# M239A.net
KiCad netlist of a schematic drawn in EAGLE
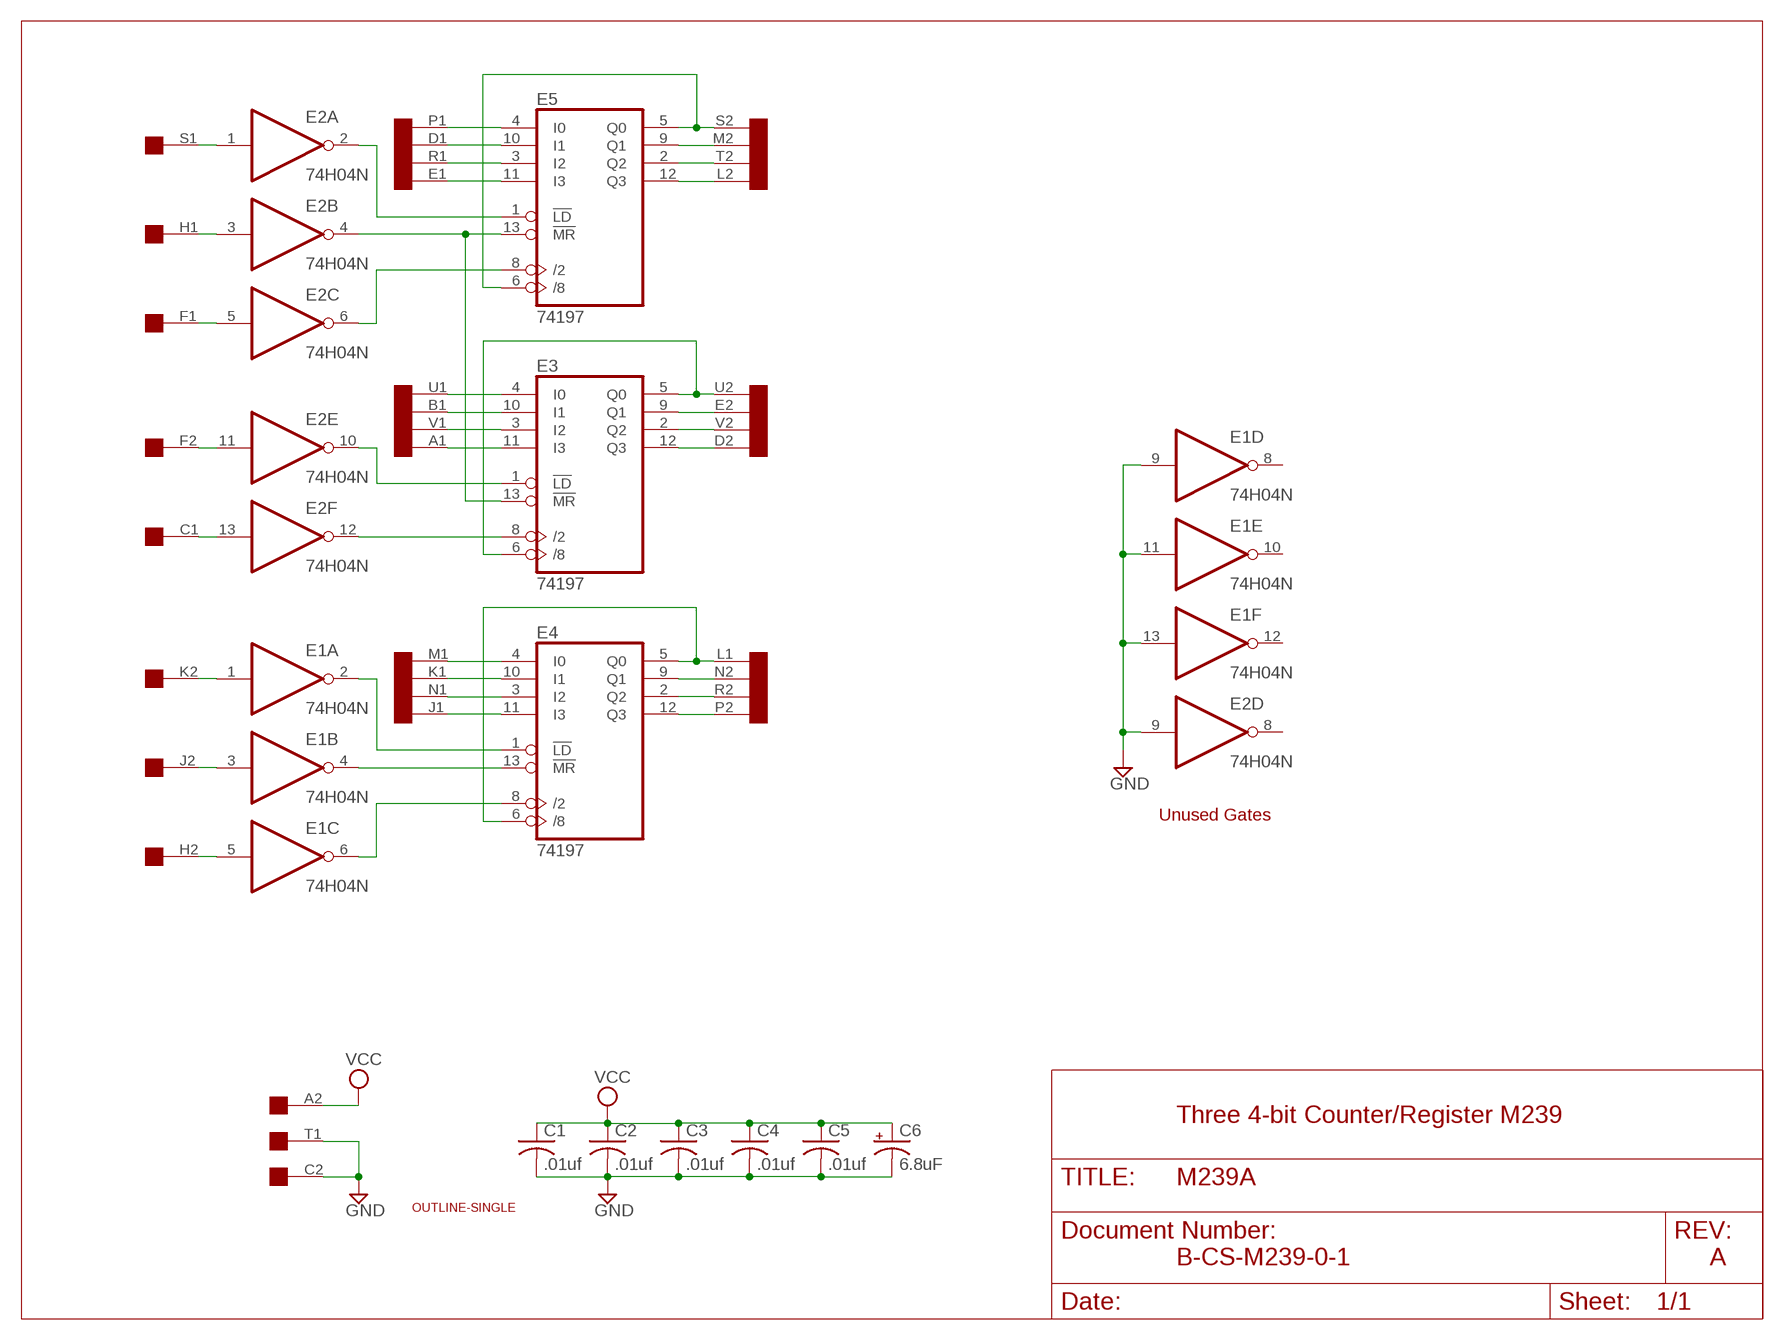
[diagram p0: schematic, sheet 1]

(export (version "E")
  (design (tool "Eeschema 10.0.6"))
  (components
    (comp (ref "C1")
      (value ".01uf")
      (footprint "eagle-import:C050-025X075")
      (libsource (lib "eagle-import") (part "C-US050-025X075"))
    )
    (comp (ref "C2")
      (value ".01uf")
      (footprint "eagle-import:C050-025X075")
      (libsource (lib "eagle-import") (part "C-US050-025X075"))
    )
    (comp (ref "C3")
      (value ".01uf")
      (footprint "eagle-import:C050-025X075")
      (libsource (lib "eagle-import") (part "C-US050-025X075"))
    )
    (comp (ref "C4")
      (value ".01uf")
      (footprint "eagle-import:C050-025X075")
      (libsource (lib "eagle-import") (part "C-US050-025X075"))
    )
    (comp (ref "C5")
      (value ".01uf")
      (footprint "eagle-import:C050-025X075")
      (libsource (lib "eagle-import") (part "C-US050-025X075"))
    )
    (comp (ref "C6")
      (value "6.8uF")
      (footprint "eagle-import:E22-6")
      (libsource (lib "eagle-import") (part "CPOL-USE22-6AXIAL"))
    )
    (comp (ref "E1")
      (value "74H04N")
      (footprint "eagle-import:DIL14")
      (libsource (lib "eagle-import") (part "7404N"))
    )
    (comp (ref "E2")
      (value "74H04N")
      (footprint "eagle-import:DIL14")
      (libsource (lib "eagle-import") (part "7404N"))
    )
    (comp (ref "E3")
      (value "74197")
      (footprint "eagle-import:DIL14")
      (libsource (lib "eagle-import") (part "74LS197"))
    )
    (comp (ref "E4")
      (value "74197")
      (footprint "eagle-import:DIL14")
      (libsource (lib "eagle-import") (part "74LS197"))
    )
    (comp (ref "E5")
      (value "74197")
      (footprint "eagle-import:DIL14")
      (libsource (lib "eagle-import") (part "74LS197"))
    )
    (comp (ref "U$1")
      (value "OUTLINE-SINGLE")
      (footprint "eagle-import:SINGLE")
      (libsource (lib "eagle-import") (part "OUTLINE-SINGLE"))
    )
    (comp (ref "U$4")
      (value "SINGLE")
      (footprint "eagle-import:EDGE-CON2")
      (libsource (lib "eagle-import") (part "SINGLE"))
    )
  )
  (nets
    (net (code "1") (name "GND") (class "Default")
      (node (ref "C1") (pin "2") (pinfunction "2_2") (pintype "passive"))
      (node (ref "C2") (pin "2") (pinfunction "2_2") (pintype "passive"))
      (node (ref "C3") (pin "2") (pinfunction "2_2") (pintype "passive"))
      (node (ref "C4") (pin "2") (pinfunction "2_2") (pintype "passive"))
      (node (ref "C5") (pin "2") (pinfunction "2_2") (pintype "passive"))
      (node (ref "C6") (pin "-") (pinfunction "-_-") (pintype "passive"))
      (node (ref "E1") (pin "11") (pinfunction "I_11") (pintype "input"))
      (node (ref "E1") (pin "13") (pinfunction "I_13") (pintype "input"))
      (node (ref "E1") (pin "9") (pinfunction "I_9") (pintype "input"))
      (node (ref "E2") (pin "9") (pinfunction "I_9") (pintype "input"))
      (node (ref "U$4") (pin "C2") (pinfunction "1_C2") (pintype "bidirectional"))
      (node (ref "U$4") (pin "T1") (pinfunction "1_T1") (pintype "bidirectional"))
    )
    (net (code "2") (name "Net-(E1A-I)") (class "Default")
      (node (ref "E1") (pin "1") (pinfunction "I_1") (pintype "input"))
      (node (ref "U$4") (pin "K2") (pinfunction "1_K2") (pintype "bidirectional"))
    )
    (net (code "3") (name "Net-(E1A-O)") (class "Default")
      (node (ref "E1") (pin "2") (pinfunction "O_2") (pintype "output"))
      (node (ref "E4") (pin "1") (pinfunction "~{LD}_1") (pintype "input"))
    )
    (net (code "4") (name "Net-(E1B-I)") (class "Default")
      (node (ref "E1") (pin "3") (pinfunction "I_3") (pintype "input"))
      (node (ref "U$4") (pin "J2") (pinfunction "1_J2") (pintype "bidirectional"))
    )
    (net (code "5") (name "Net-(E1B-O)") (class "Default")
      (node (ref "E1") (pin "4") (pinfunction "O_4") (pintype "output"))
      (node (ref "E4") (pin "13") (pinfunction "~{MR}_13") (pintype "input"))
    )
    (net (code "6") (name "Net-(E1C-I)") (class "Default")
      (node (ref "E1") (pin "5") (pinfunction "I_5") (pintype "input"))
      (node (ref "U$4") (pin "H2") (pinfunction "1_H2") (pintype "bidirectional"))
    )
    (net (code "7") (name "Net-(E1C-O)") (class "Default")
      (node (ref "E1") (pin "6") (pinfunction "O_6") (pintype "output"))
      (node (ref "E4") (pin "8") (pinfunction "/2_8") (pintype "bidirectional"))
    )
    (net (code "8") (name "Net-(E2A-I)") (class "Default")
      (node (ref "E2") (pin "1") (pinfunction "I_1") (pintype "input"))
      (node (ref "U$4") (pin "S1") (pinfunction "1_S1") (pintype "bidirectional"))
    )
    (net (code "9") (name "Net-(E2A-O)") (class "Default")
      (node (ref "E2") (pin "2") (pinfunction "O_2") (pintype "output"))
      (node (ref "E5") (pin "1") (pinfunction "~{LD}_1") (pintype "input"))
    )
    (net (code "10") (name "Net-(E2B-I)") (class "Default")
      (node (ref "E2") (pin "3") (pinfunction "I_3") (pintype "input"))
      (node (ref "U$4") (pin "H1") (pinfunction "1_H1") (pintype "bidirectional"))
    )
    (net (code "11") (name "Net-(E2B-O)") (class "Default")
      (node (ref "E2") (pin "4") (pinfunction "O_4") (pintype "output"))
      (node (ref "E3") (pin "13") (pinfunction "~{MR}_13") (pintype "input"))
      (node (ref "E5") (pin "13") (pinfunction "~{MR}_13") (pintype "input"))
    )
    (net (code "12") (name "Net-(E2C-I)") (class "Default")
      (node (ref "E2") (pin "5") (pinfunction "I_5") (pintype "input"))
      (node (ref "U$4") (pin "F1") (pinfunction "1_F1") (pintype "bidirectional"))
    )
    (net (code "13") (name "Net-(E2C-O)") (class "Default")
      (node (ref "E2") (pin "6") (pinfunction "O_6") (pintype "output"))
      (node (ref "E5") (pin "8") (pinfunction "/2_8") (pintype "bidirectional"))
    )
    (net (code "14") (name "Net-(E2E-I)") (class "Default")
      (node (ref "E2") (pin "11") (pinfunction "I_11") (pintype "input"))
      (node (ref "U$4") (pin "F2") (pinfunction "1_F2") (pintype "bidirectional"))
    )
    (net (code "15") (name "Net-(E2E-O)") (class "Default")
      (node (ref "E2") (pin "10") (pinfunction "O_10") (pintype "output"))
      (node (ref "E3") (pin "1") (pinfunction "~{LD}_1") (pintype "input"))
    )
    (net (code "16") (name "Net-(E2F-I)") (class "Default")
      (node (ref "E2") (pin "13") (pinfunction "I_13") (pintype "input"))
      (node (ref "U$4") (pin "C1") (pinfunction "1_C1") (pintype "bidirectional"))
    )
    (net (code "17") (name "Net-(E2F-O)") (class "Default")
      (node (ref "E2") (pin "12") (pinfunction "O_12") (pintype "output"))
      (node (ref "E3") (pin "8") (pinfunction "/2_8") (pintype "bidirectional"))
    )
    (net (code "18") (name "Net-(E3A-I0)") (class "Default")
      (node (ref "E3") (pin "4") (pinfunction "I0_4") (pintype "input"))
      (node (ref "U$4") (pin "U1") (pinfunction "1_U1") (pintype "bidirectional"))
    )
    (net (code "19") (name "Net-(E3A-I1)") (class "Default")
      (node (ref "E3") (pin "10") (pinfunction "I1_10") (pintype "input"))
      (node (ref "U$4") (pin "B1") (pinfunction "1_B1") (pintype "bidirectional"))
    )
    (net (code "20") (name "Net-(E3A-I2)") (class "Default")
      (node (ref "E3") (pin "3") (pinfunction "I2_3") (pintype "input"))
      (node (ref "U$4") (pin "V1") (pinfunction "1_V1") (pintype "bidirectional"))
    )
    (net (code "21") (name "Net-(E3A-I3)") (class "Default")
      (node (ref "E3") (pin "11") (pinfunction "I3_11") (pintype "input"))
      (node (ref "U$4") (pin "A1") (pinfunction "1_A1") (pintype "bidirectional"))
    )
    (net (code "22") (name "Net-(E3A-Q0)") (class "Default")
      (node (ref "E3") (pin "5") (pinfunction "Q0_5") (pintype "output"))
      (node (ref "E3") (pin "6") (pinfunction "/8_6") (pintype "bidirectional"))
      (node (ref "U$4") (pin "U2") (pinfunction "1_U2") (pintype "bidirectional"))
    )
    (net (code "23") (name "Net-(E3A-Q1)") (class "Default")
      (node (ref "E3") (pin "9") (pinfunction "Q1_9") (pintype "output"))
      (node (ref "U$4") (pin "E2") (pinfunction "1_E2") (pintype "bidirectional"))
    )
    (net (code "24") (name "Net-(E3A-Q2)") (class "Default")
      (node (ref "E3") (pin "2") (pinfunction "Q2_2") (pintype "output"))
      (node (ref "U$4") (pin "V2") (pinfunction "1_V2") (pintype "bidirectional"))
    )
    (net (code "25") (name "Net-(E3A-Q3)") (class "Default")
      (node (ref "E3") (pin "12") (pinfunction "Q3_12") (pintype "output"))
      (node (ref "U$4") (pin "D2") (pinfunction "1_D2") (pintype "bidirectional"))
    )
    (net (code "26") (name "Net-(E4A-I0)") (class "Default")
      (node (ref "E4") (pin "4") (pinfunction "I0_4") (pintype "input"))
      (node (ref "U$4") (pin "M1") (pinfunction "1_M1") (pintype "bidirectional"))
    )
    (net (code "27") (name "Net-(E4A-I1)") (class "Default")
      (node (ref "E4") (pin "10") (pinfunction "I1_10") (pintype "input"))
      (node (ref "U$4") (pin "K1") (pinfunction "1_K1") (pintype "bidirectional"))
    )
    (net (code "28") (name "Net-(E4A-I2)") (class "Default")
      (node (ref "E4") (pin "3") (pinfunction "I2_3") (pintype "input"))
      (node (ref "U$4") (pin "N1") (pinfunction "1_N1") (pintype "bidirectional"))
    )
    (net (code "29") (name "Net-(E4A-I3)") (class "Default")
      (node (ref "E4") (pin "11") (pinfunction "I3_11") (pintype "input"))
      (node (ref "U$4") (pin "J1") (pinfunction "1_J1") (pintype "bidirectional"))
    )
    (net (code "30") (name "Net-(E4A-Q0)") (class "Default")
      (node (ref "E4") (pin "5") (pinfunction "Q0_5") (pintype "output"))
      (node (ref "E4") (pin "6") (pinfunction "/8_6") (pintype "bidirectional"))
      (node (ref "U$4") (pin "L1") (pinfunction "1_L1") (pintype "bidirectional"))
    )
    (net (code "31") (name "Net-(E4A-Q1)") (class "Default")
      (node (ref "E4") (pin "9") (pinfunction "Q1_9") (pintype "output"))
      (node (ref "U$4") (pin "N2") (pinfunction "1_N2") (pintype "bidirectional"))
    )
    (net (code "32") (name "Net-(E4A-Q2)") (class "Default")
      (node (ref "E4") (pin "2") (pinfunction "Q2_2") (pintype "output"))
      (node (ref "U$4") (pin "R2") (pinfunction "1_R2") (pintype "bidirectional"))
    )
    (net (code "33") (name "Net-(E4A-Q3)") (class "Default")
      (node (ref "E4") (pin "12") (pinfunction "Q3_12") (pintype "output"))
      (node (ref "U$4") (pin "P2") (pinfunction "1_P2") (pintype "bidirectional"))
    )
    (net (code "34") (name "Net-(E5A-I0)") (class "Default")
      (node (ref "E5") (pin "4") (pinfunction "I0_4") (pintype "input"))
      (node (ref "U$4") (pin "P1") (pinfunction "1_P1") (pintype "bidirectional"))
    )
    (net (code "35") (name "Net-(E5A-I1)") (class "Default")
      (node (ref "E5") (pin "10") (pinfunction "I1_10") (pintype "input"))
      (node (ref "U$4") (pin "D1") (pinfunction "1_D1") (pintype "bidirectional"))
    )
    (net (code "36") (name "Net-(E5A-I2)") (class "Default")
      (node (ref "E5") (pin "3") (pinfunction "I2_3") (pintype "input"))
      (node (ref "U$4") (pin "R1") (pinfunction "1_R1") (pintype "bidirectional"))
    )
    (net (code "37") (name "Net-(E5A-I3)") (class "Default")
      (node (ref "E5") (pin "11") (pinfunction "I3_11") (pintype "input"))
      (node (ref "U$4") (pin "E1") (pinfunction "1_E1") (pintype "bidirectional"))
    )
    (net (code "38") (name "Net-(E5A-Q0)") (class "Default")
      (node (ref "E5") (pin "5") (pinfunction "Q0_5") (pintype "output"))
      (node (ref "E5") (pin "6") (pinfunction "/8_6") (pintype "bidirectional"))
      (node (ref "U$4") (pin "S2") (pinfunction "1_S2") (pintype "bidirectional"))
    )
    (net (code "39") (name "Net-(E5A-Q1)") (class "Default")
      (node (ref "E5") (pin "9") (pinfunction "Q1_9") (pintype "output"))
      (node (ref "U$4") (pin "M2") (pinfunction "1_M2") (pintype "bidirectional"))
    )
    (net (code "40") (name "Net-(E5A-Q2)") (class "Default")
      (node (ref "E5") (pin "2") (pinfunction "Q2_2") (pintype "output"))
      (node (ref "U$4") (pin "T2") (pinfunction "1_T2") (pintype "bidirectional"))
    )
    (net (code "41") (name "Net-(E5A-Q3)") (class "Default")
      (node (ref "E5") (pin "12") (pinfunction "Q3_12") (pintype "output"))
      (node (ref "U$4") (pin "L2") (pinfunction "1_L2") (pintype "bidirectional"))
    )
    (net (code "42") (name "VCC") (class "Default")
      (node (ref "C1") (pin "1") (pinfunction "1_1") (pintype "passive"))
      (node (ref "C2") (pin "1") (pinfunction "1_1") (pintype "passive"))
      (node (ref "C3") (pin "1") (pinfunction "1_1") (pintype "passive"))
      (node (ref "C4") (pin "1") (pinfunction "1_1") (pintype "passive"))
      (node (ref "C5") (pin "1") (pinfunction "1_1") (pintype "passive"))
      (node (ref "C6") (pin "+") (pinfunction "+_+") (pintype "passive"))
      (node (ref "U$4") (pin "A2") (pinfunction "1_A2") (pintype "bidirectional"))
    )
    (net (code "43") (name "unconnected-(E1D-O-Pad8)") (class "Default")
      (node (ref "E1") (pin "8") (pinfunction "O_8") (pintype "output"))
    )
    (net (code "44") (name "unconnected-(E1E-O-Pad10)") (class "Default")
      (node (ref "E1") (pin "10") (pinfunction "O_10") (pintype "output"))
    )
    (net (code "45") (name "unconnected-(E1F-O-Pad12)") (class "Default")
      (node (ref "E1") (pin "12") (pinfunction "O_12") (pintype "output"))
    )
    (net (code "46") (name "unconnected-(E2D-O-Pad8)") (class "Default")
      (node (ref "E2") (pin "8") (pinfunction "O_8") (pintype "output"))
    )
  )
)
